# Licznik_sekund.net
KiCad netlist of a schematic drawn in Altium Designer
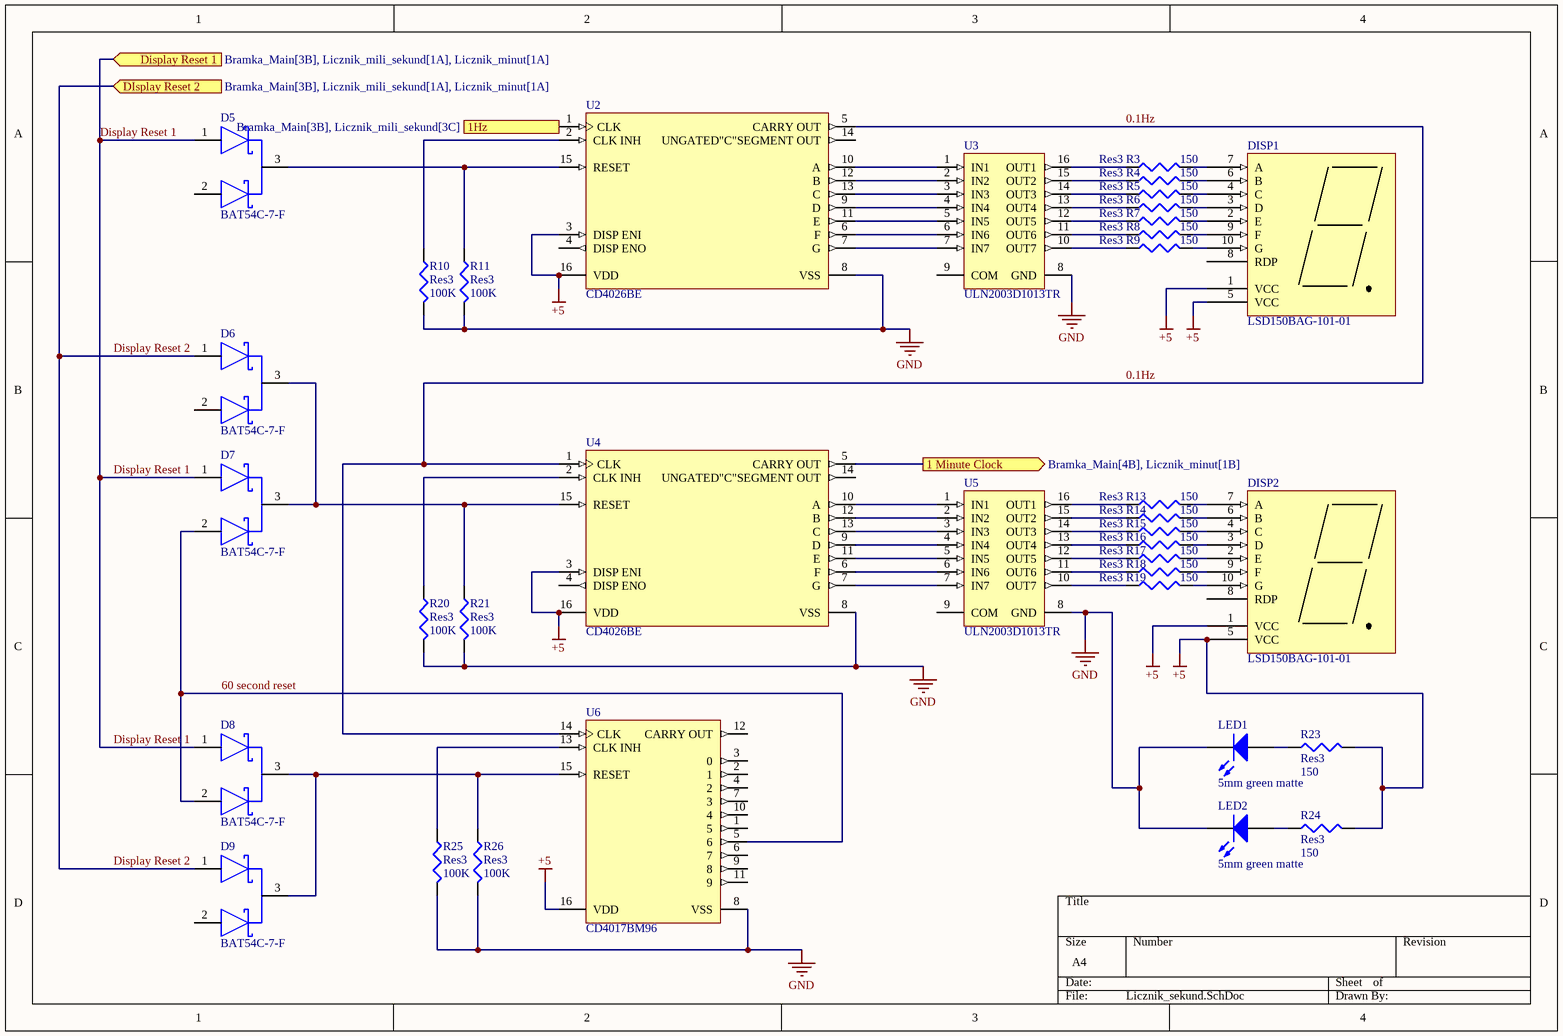
[diagram p0: Licznik_sekund.SchDoc]

(export (version "E")
  (design (tool "Eeschema 10.0.6"))
  (components
    (comp (ref "D5")
      (value "BAT54C-7-F")
      (footprint "FP-SOT23-IPC_B")
      (description "DIODE ARRAY SCHOTTKY 30V SOT23-3")
      (libsource (lib "Altium Content Vault") (part "3eac2aa0c1ac86323ecc23460aa29c6"))
    )
    (comp (ref "D6")
      (value "BAT54C-7-F")
      (footprint "FP-SOT23-IPC_B")
      (description "DIODE ARRAY SCHOTTKY 30V SOT23-3")
      (libsource (lib "Altium Content Vault") (part "3eac2aa0c1ac86323ecc23460aa29c6"))
    )
    (comp (ref "D7")
      (value "BAT54C-7-F")
      (footprint "FP-SOT23-IPC_B")
      (description "DIODE ARRAY SCHOTTKY 30V SOT23-3")
      (libsource (lib "Altium Content Vault") (part "3eac2aa0c1ac86323ecc23460aa29c6"))
    )
    (comp (ref "D8")
      (value "BAT54C-7-F")
      (footprint "FP-SOT23-IPC_B")
      (description "DIODE ARRAY SCHOTTKY 30V SOT23-3")
      (libsource (lib "Altium Content Vault") (part "3eac2aa0c1ac86323ecc23460aa29c6"))
    )
    (comp (ref "D9")
      (value "BAT54C-7-F")
      (footprint "FP-SOT23-IPC_B")
      (description "DIODE ARRAY SCHOTTKY 30V SOT23-3")
      (libsource (lib "Altium Content Vault") (part "3eac2aa0c1ac86323ecc23460aa29c6"))
    )
    (comp (ref "DISP1")
      (value "LSD150BAG-101-01")
      (footprint "7 segment display")
      (description "7 segment display 1.5 inch")
      (libsource (lib "WUST") (part "LSD150BAG-101-01-Symbol-1"))
    )
    (comp (ref "DISP2")
      (value "LSD150BAG-101-01")
      (footprint "7 segment display")
      (description "7 segment display 1.5 inch")
      (libsource (lib "WUST") (part "LSD150BAG-101-01-Symbol-1"))
    )
    (comp (ref "LED1")
      (value "5mm green matte")
      (footprint "Type 5mm")
      (description "THT LED round mono-color color lens, WL-TMRW, Bright Green")
      (fields (field (name "PARTNUMBER") "151051VS04000") (field (name "MANUFACTURER") "Wuerth Elektronik"))
      (libsource (lib "Altium Content Vault") (part "WE-LED_K1A2-2"))
    )
    (comp (ref "LED2")
      (value "5mm green matte")
      (footprint "Type 5mm")
      (description "THT LED round mono-color color lens, WL-TMRW, Bright Green")
      (fields (field (name "PARTNUMBER") "151051VS04000") (field (name "MANUFACTURER") "Wuerth Elektronik"))
      (libsource (lib "Altium Content Vault") (part "WE-LED_K1A2-2"))
    )
    (comp (ref "R3")
      (value "Res3")
      (footprint "6-0805_M")
      (description "Resistor")
      (fields (field (name "ALTIUM_VALUE") "150") (field (name "PUBLISHER") "Altium Limited"))
      (libsource (lib "Miscellaneous Devices") (part "Res3"))
    )
    (comp (ref "R4")
      (value "Res3")
      (footprint "6-0805_M")
      (description "Resistor")
      (fields (field (name "ALTIUM_VALUE") "150") (field (name "PUBLISHER") "Altium Limited"))
      (libsource (lib "Miscellaneous Devices") (part "Res3"))
    )
    (comp (ref "R5")
      (value "Res3")
      (footprint "6-0805_M")
      (description "Resistor")
      (fields (field (name "ALTIUM_VALUE") "150") (field (name "PUBLISHER") "Altium Limited"))
      (libsource (lib "Miscellaneous Devices") (part "Res3"))
    )
    (comp (ref "R6")
      (value "Res3")
      (footprint "6-0805_M")
      (description "Resistor")
      (fields (field (name "ALTIUM_VALUE") "150") (field (name "PUBLISHER") "Altium Limited"))
      (libsource (lib "Miscellaneous Devices") (part "Res3"))
    )
    (comp (ref "R7")
      (value "Res3")
      (footprint "6-0805_M")
      (description "Resistor")
      (fields (field (name "ALTIUM_VALUE") "150") (field (name "PUBLISHER") "Altium Limited"))
      (libsource (lib "Miscellaneous Devices") (part "Res3"))
    )
    (comp (ref "R8")
      (value "Res3")
      (footprint "6-0805_M")
      (description "Resistor")
      (fields (field (name "ALTIUM_VALUE") "150") (field (name "PUBLISHER") "Altium Limited"))
      (libsource (lib "Miscellaneous Devices") (part "Res3"))
    )
    (comp (ref "R9")
      (value "Res3")
      (footprint "6-0805_M")
      (description "Resistor")
      (fields (field (name "ALTIUM_VALUE") "150") (field (name "PUBLISHER") "Altium Limited"))
      (libsource (lib "Miscellaneous Devices") (part "Res3"))
    )
    (comp (ref "R10")
      (value "Res3")
      (footprint "J1-0603")
      (description "Resistor")
      (fields (field (name "ALTIUM_VALUE") "100K") (field (name "PUBLISHER") "Altium Limited"))
      (libsource (lib "Miscellaneous Devices") (part "Res3"))
    )
    (comp (ref "R11")
      (value "Res3")
      (footprint "J1-0603")
      (description "Resistor")
      (fields (field (name "ALTIUM_VALUE") "100K") (field (name "PUBLISHER") "Altium Limited"))
      (libsource (lib "Miscellaneous Devices") (part "Res3"))
    )
    (comp (ref "R13")
      (value "Res3")
      (footprint "6-0805_M")
      (description "Resistor")
      (fields (field (name "ALTIUM_VALUE") "150") (field (name "PUBLISHER") "Altium Limited"))
      (libsource (lib "Miscellaneous Devices") (part "Res3"))
    )
    (comp (ref "R14")
      (value "Res3")
      (footprint "6-0805_M")
      (description "Resistor")
      (fields (field (name "ALTIUM_VALUE") "150") (field (name "PUBLISHER") "Altium Limited"))
      (libsource (lib "Miscellaneous Devices") (part "Res3"))
    )
    (comp (ref "R15")
      (value "Res3")
      (footprint "6-0805_M")
      (description "Resistor")
      (fields (field (name "ALTIUM_VALUE") "150") (field (name "PUBLISHER") "Altium Limited"))
      (libsource (lib "Miscellaneous Devices") (part "Res3"))
    )
    (comp (ref "R16")
      (value "Res3")
      (footprint "6-0805_M")
      (description "Resistor")
      (fields (field (name "ALTIUM_VALUE") "150") (field (name "PUBLISHER") "Altium Limited"))
      (libsource (lib "Miscellaneous Devices") (part "Res3"))
    )
    (comp (ref "R17")
      (value "Res3")
      (footprint "6-0805_M")
      (description "Resistor")
      (fields (field (name "ALTIUM_VALUE") "150") (field (name "PUBLISHER") "Altium Limited"))
      (libsource (lib "Miscellaneous Devices") (part "Res3"))
    )
    (comp (ref "R18")
      (value "Res3")
      (footprint "6-0805_M")
      (description "Resistor")
      (fields (field (name "ALTIUM_VALUE") "150") (field (name "PUBLISHER") "Altium Limited"))
      (libsource (lib "Miscellaneous Devices") (part "Res3"))
    )
    (comp (ref "R19")
      (value "Res3")
      (footprint "6-0805_M")
      (description "Resistor")
      (fields (field (name "ALTIUM_VALUE") "150") (field (name "PUBLISHER") "Altium Limited"))
      (libsource (lib "Miscellaneous Devices") (part "Res3"))
    )
    (comp (ref "R20")
      (value "Res3")
      (footprint "J1-0603")
      (description "Resistor")
      (fields (field (name "ALTIUM_VALUE") "100K") (field (name "PUBLISHER") "Altium Limited"))
      (libsource (lib "Miscellaneous Devices") (part "Res3"))
    )
    (comp (ref "R21")
      (value "Res3")
      (footprint "J1-0603")
      (description "Resistor")
      (fields (field (name "ALTIUM_VALUE") "100K") (field (name "PUBLISHER") "Altium Limited"))
      (libsource (lib "Miscellaneous Devices") (part "Res3"))
    )
    (comp (ref "R23")
      (value "Res3")
      (footprint "6-0805_M")
      (description "Resistor")
      (fields (field (name "ALTIUM_VALUE") "150") (field (name "PUBLISHER") "Altium Limited"))
      (libsource (lib "Miscellaneous Devices") (part "Res3"))
    )
    (comp (ref "R24")
      (value "Res3")
      (footprint "6-0805_M")
      (description "Resistor")
      (fields (field (name "ALTIUM_VALUE") "150") (field (name "PUBLISHER") "Altium Limited"))
      (libsource (lib "Miscellaneous Devices") (part "Res3"))
    )
    (comp (ref "R25")
      (value "Res3")
      (footprint "J1-0603")
      (description "Resistor")
      (fields (field (name "ALTIUM_VALUE") "100K") (field (name "PUBLISHER") "Altium Limited"))
      (libsource (lib "Miscellaneous Devices") (part "Res3"))
    )
    (comp (ref "R26")
      (value "Res3")
      (footprint "J1-0603")
      (description "Resistor")
      (fields (field (name "ALTIUM_VALUE") "100K") (field (name "PUBLISHER") "Altium Limited"))
      (libsource (lib "Miscellaneous Devices") (part "Res3"))
    )
    (comp (ref "U2")
      (value "CD4026BE")
      (footprint "N0016A")
      (fields
        (field (name "MANUFACTURER") "Texas Instruments")
        (field (name "GENERIC PART NUMBER") "CD4026B")
      )
      (libsource (lib "Altium Content Vault") (part "TI-CD4026B-16"))
    )
    (comp (ref "U3")
      (value "ULN2003D1013TR")
      (footprint "STM-SO-16_M")
      (fields (field (name "MANUFACTURER") "STMicroelectronics"))
      (libsource (lib "Altium Content Vault") (part "STM-ULN2003A-PDIP-16"))
    )
    (comp (ref "U4")
      (value "CD4026BE")
      (footprint "N0016A")
      (fields
        (field (name "MANUFACTURER") "Texas Instruments")
        (field (name "GENERIC PART NUMBER") "CD4026B")
      )
      (libsource (lib "Altium Content Vault") (part "TI-CD4026B-16"))
    )
    (comp (ref "U5")
      (value "ULN2003D1013TR")
      (footprint "STM-SO-16_M")
      (fields (field (name "MANUFACTURER") "STMicroelectronics"))
      (libsource (lib "Altium Content Vault") (part "STM-ULN2003A-PDIP-16"))
    )
    (comp (ref "U6")
      (value "CD4017BM96")
      (footprint "D0016A_L")
      (description "CMOS Decade Counter with 10 Decoded Outputs, D0016A, LARGE T&R")
      (fields
        (field (name "GENERIC PART NUMBER") "CD4017B")
        (field (name "MANUFACTURER") "Texas Instruments")
      )
      (libsource (lib "Altium Content Vault") (part "TI-CD4017B-16"))
    )
  )
  (nets
    (net (code "1") (name "+5") (class "Default")
      (node (ref "DISP1") (pin "1") (pinfunction "VCC_1") (pintype "power_in"))
      (node (ref "DISP1") (pin "5") (pinfunction "VCC_5") (pintype "power_in"))
      (node (ref "DISP2") (pin "1") (pinfunction "VCC_1") (pintype "power_in"))
      (node (ref "DISP2") (pin "5") (pinfunction "VCC_5") (pintype "power_in"))
      (node (ref "R23") (pin "2") (pinfunction "2_2") (pintype "passive"))
      (node (ref "R24") (pin "2") (pinfunction "2_2") (pintype "passive"))
      (node (ref "U2") (pin "16") (pinfunction "VDD_16") (pintype "power_in"))
      (node (ref "U2") (pin "3") (pinfunction "DISP_ENI_3") (pintype "input"))
      (node (ref "U4") (pin "16") (pinfunction "VDD_16") (pintype "power_in"))
      (node (ref "U4") (pin "3") (pinfunction "DISP_ENI_3") (pintype "input"))
      (node (ref "U6") (pin "16") (pinfunction "VDD_16") (pintype "power_in"))
    )
    (net (code "2") (name "/0.1Hz") (class "Default")
      (node (ref "U2") (pin "5") (pinfunction "CARRY_OUT_5") (pintype "output"))
      (node (ref "U4") (pin "1") (pinfunction "CLK_1") (pintype "input"))
      (node (ref "U6") (pin "14") (pinfunction "CLK_14") (pintype "input"))
    )
    (net (code "3") (name "/1 Minute Clock") (class "Default")
      (node (ref "U4") (pin "5") (pinfunction "CARRY_OUT_5") (pintype "output"))
    )
    (net (code "4") (name "/1Hz") (class "Default")
      (node (ref "U2") (pin "1") (pinfunction "CLK_1") (pintype "input"))
    )
    (net (code "5") (name "/60 second reset") (class "Default")
      (node (ref "D7") (pin "2") (pinfunction "2_ANODE_2") (pintype "passive"))
      (node (ref "D8") (pin "2") (pinfunction "2_ANODE_2") (pintype "passive"))
      (node (ref "U6") (pin "5") (pinfunction "6_5") (pintype "output"))
    )
    (net (code "6") (name "/Display Reset 1") (class "Default")
      (node (ref "D5") (pin "1") (pinfunction "1_ANODE_1") (pintype "passive"))
      (node (ref "D7") (pin "1") (pinfunction "1_ANODE_1") (pintype "passive"))
      (node (ref "D8") (pin "1") (pinfunction "1_ANODE_1") (pintype "passive"))
    )
    (net (code "7") (name "/Display Reset 2") (class "Default")
      (node (ref "D6") (pin "1") (pinfunction "1_ANODE_1") (pintype "passive"))
      (node (ref "D9") (pin "1") (pinfunction "1_ANODE_1") (pintype "passive"))
    )
    (net (code "8") (name "GND") (class "Default")
      (node (ref "LED1") (pin "1") (pinfunction "K_1") (pintype "passive"))
      (node (ref "LED2") (pin "1") (pinfunction "K_1") (pintype "passive"))
      (node (ref "R10") (pin "2") (pinfunction "2_2") (pintype "passive"))
      (node (ref "R11") (pin "2") (pinfunction "2_2") (pintype "passive"))
      (node (ref "R20") (pin "2") (pinfunction "2_2") (pintype "passive"))
      (node (ref "R21") (pin "2") (pinfunction "2_2") (pintype "passive"))
      (node (ref "R25") (pin "2") (pinfunction "2_2") (pintype "passive"))
      (node (ref "R26") (pin "2") (pinfunction "2_2") (pintype "passive"))
      (node (ref "U2") (pin "8") (pinfunction "VSS_8") (pintype "power_in"))
      (node (ref "U3") (pin "8") (pinfunction "GND_8") (pintype "power_in"))
      (node (ref "U4") (pin "8") (pinfunction "VSS_8") (pintype "power_in"))
      (node (ref "U5") (pin "8") (pinfunction "GND_8") (pintype "power_in"))
      (node (ref "U6") (pin "8") (pinfunction "VSS_8") (pintype "power_in"))
    )
    (net (code "9") (name "Net-(D5-COMMON_CATHODE)") (class "Default")
      (node (ref "D5") (pin "3") (pinfunction "COMMON_CATHODE_3") (pintype "passive"))
      (node (ref "R11") (pin "1") (pinfunction "1_1") (pintype "passive"))
      (node (ref "U2") (pin "15") (pinfunction "RESET_15") (pintype "input"))
    )
    (net (code "10") (name "Net-(D6-COMMON_CATHODE)") (class "Default")
      (node (ref "D6") (pin "3") (pinfunction "COMMON_CATHODE_3") (pintype "passive"))
      (node (ref "D7") (pin "3") (pinfunction "COMMON_CATHODE_3") (pintype "passive"))
      (node (ref "R21") (pin "1") (pinfunction "1_1") (pintype "passive"))
      (node (ref "U4") (pin "15") (pinfunction "RESET_15") (pintype "input"))
    )
    (net (code "11") (name "Net-(D8-COMMON_CATHODE)") (class "Default")
      (node (ref "D8") (pin "3") (pinfunction "COMMON_CATHODE_3") (pintype "passive"))
      (node (ref "D9") (pin "3") (pinfunction "COMMON_CATHODE_3") (pintype "passive"))
      (node (ref "R26") (pin "1") (pinfunction "1_1") (pintype "passive"))
      (node (ref "U6") (pin "15") (pinfunction "RESET_15") (pintype "input"))
    )
    (net (code "12") (name "Net-(DISP1-A)") (class "Default")
      (node (ref "DISP1") (pin "7") (pinfunction "A_7") (pintype "input"))
      (node (ref "R3") (pin "2") (pinfunction "2_2") (pintype "passive"))
    )
    (net (code "13") (name "Net-(DISP1-B)") (class "Default")
      (node (ref "DISP1") (pin "6") (pinfunction "B_6") (pintype "input"))
      (node (ref "R4") (pin "2") (pinfunction "2_2") (pintype "passive"))
    )
    (net (code "14") (name "Net-(DISP1-C)") (class "Default")
      (node (ref "DISP1") (pin "4") (pinfunction "C_4") (pintype "input"))
      (node (ref "R5") (pin "2") (pinfunction "2_2") (pintype "passive"))
    )
    (net (code "15") (name "Net-(DISP1-D)") (class "Default")
      (node (ref "DISP1") (pin "3") (pinfunction "D_3") (pintype "input"))
      (node (ref "R6") (pin "2") (pinfunction "2_2") (pintype "passive"))
    )
    (net (code "16") (name "Net-(DISP1-E)") (class "Default")
      (node (ref "DISP1") (pin "2") (pinfunction "E_2") (pintype "input"))
      (node (ref "R7") (pin "2") (pinfunction "2_2") (pintype "passive"))
    )
    (net (code "17") (name "Net-(DISP1-F)") (class "Default")
      (node (ref "DISP1") (pin "9") (pinfunction "F_9") (pintype "input"))
      (node (ref "R8") (pin "2") (pinfunction "2_2") (pintype "passive"))
    )
    (net (code "18") (name "Net-(DISP1-G)") (class "Default")
      (node (ref "DISP1") (pin "10") (pinfunction "G_10") (pintype "input"))
      (node (ref "R9") (pin "2") (pinfunction "2_2") (pintype "passive"))
    )
    (net (code "19") (name "Net-(DISP2-A)") (class "Default")
      (node (ref "DISP2") (pin "7") (pinfunction "A_7") (pintype "input"))
      (node (ref "R13") (pin "2") (pinfunction "2_2") (pintype "passive"))
    )
    (net (code "20") (name "Net-(DISP2-B)") (class "Default")
      (node (ref "DISP2") (pin "6") (pinfunction "B_6") (pintype "input"))
      (node (ref "R14") (pin "2") (pinfunction "2_2") (pintype "passive"))
    )
    (net (code "21") (name "Net-(DISP2-C)") (class "Default")
      (node (ref "DISP2") (pin "4") (pinfunction "C_4") (pintype "input"))
      (node (ref "R15") (pin "2") (pinfunction "2_2") (pintype "passive"))
    )
    (net (code "22") (name "Net-(DISP2-D)") (class "Default")
      (node (ref "DISP2") (pin "3") (pinfunction "D_3") (pintype "input"))
      (node (ref "R16") (pin "2") (pinfunction "2_2") (pintype "passive"))
    )
    (net (code "23") (name "Net-(DISP2-E)") (class "Default")
      (node (ref "DISP2") (pin "2") (pinfunction "E_2") (pintype "input"))
      (node (ref "R17") (pin "2") (pinfunction "2_2") (pintype "passive"))
    )
    (net (code "24") (name "Net-(DISP2-F)") (class "Default")
      (node (ref "DISP2") (pin "9") (pinfunction "F_9") (pintype "input"))
      (node (ref "R18") (pin "2") (pinfunction "2_2") (pintype "passive"))
    )
    (net (code "25") (name "Net-(DISP2-G)") (class "Default")
      (node (ref "DISP2") (pin "10") (pinfunction "G_10") (pintype "input"))
      (node (ref "R19") (pin "2") (pinfunction "2_2") (pintype "passive"))
    )
    (net (code "26") (name "Net-(LED1-A)") (class "Default")
      (node (ref "LED1") (pin "2") (pinfunction "A_2") (pintype "passive"))
      (node (ref "R23") (pin "1") (pinfunction "1_1") (pintype "passive"))
    )
    (net (code "27") (name "Net-(LED2-A)") (class "Default")
      (node (ref "LED2") (pin "2") (pinfunction "A_2") (pintype "passive"))
      (node (ref "R24") (pin "1") (pinfunction "1_1") (pintype "passive"))
    )
    (net (code "28") (name "Net-(U2-A)") (class "Default")
      (node (ref "U2") (pin "10") (pinfunction "A_10") (pintype "output"))
      (node (ref "U3") (pin "1") (pinfunction "IN1_1") (pintype "input"))
    )
    (net (code "29") (name "Net-(U2-B)") (class "Default")
      (node (ref "U2") (pin "12") (pinfunction "B_12") (pintype "output"))
      (node (ref "U3") (pin "2") (pinfunction "IN2_2") (pintype "input"))
    )
    (net (code "30") (name "Net-(U2-C)") (class "Default")
      (node (ref "U2") (pin "13") (pinfunction "C_13") (pintype "output"))
      (node (ref "U3") (pin "3") (pinfunction "IN3_3") (pintype "input"))
    )
    (net (code "31") (name "Net-(U2-CLK_INH)") (class "Default")
      (node (ref "R10") (pin "1") (pinfunction "1_1") (pintype "passive"))
      (node (ref "U2") (pin "2") (pinfunction "CLK_INH_2") (pintype "input"))
    )
    (net (code "32") (name "Net-(U2-D)") (class "Default")
      (node (ref "U2") (pin "9") (pinfunction "D_9") (pintype "output"))
      (node (ref "U3") (pin "4") (pinfunction "IN4_4") (pintype "input"))
    )
    (net (code "33") (name "Net-(U2-E)") (class "Default")
      (node (ref "U2") (pin "11") (pinfunction "E_11") (pintype "output"))
      (node (ref "U3") (pin "5") (pinfunction "IN5_5") (pintype "input"))
    )
    (net (code "34") (name "Net-(U2-F)") (class "Default")
      (node (ref "U2") (pin "6") (pinfunction "F_6") (pintype "output"))
      (node (ref "U3") (pin "6") (pinfunction "IN6_6") (pintype "input"))
    )
    (net (code "35") (name "Net-(U2-G)") (class "Default")
      (node (ref "U2") (pin "7") (pinfunction "G_7") (pintype "output"))
      (node (ref "U3") (pin "7") (pinfunction "IN7_7") (pintype "input"))
    )
    (net (code "36") (name "Net-(U3-OUT1)") (class "Default")
      (node (ref "R3") (pin "1") (pinfunction "1_1") (pintype "passive"))
      (node (ref "U3") (pin "16") (pinfunction "OUT1_16") (pintype "output"))
    )
    (net (code "37") (name "Net-(U3-OUT2)") (class "Default")
      (node (ref "R4") (pin "1") (pinfunction "1_1") (pintype "passive"))
      (node (ref "U3") (pin "15") (pinfunction "OUT2_15") (pintype "output"))
    )
    (net (code "38") (name "Net-(U3-OUT3)") (class "Default")
      (node (ref "R5") (pin "1") (pinfunction "1_1") (pintype "passive"))
      (node (ref "U3") (pin "14") (pinfunction "OUT3_14") (pintype "output"))
    )
    (net (code "39") (name "Net-(U3-OUT4)") (class "Default")
      (node (ref "R6") (pin "1") (pinfunction "1_1") (pintype "passive"))
      (node (ref "U3") (pin "13") (pinfunction "OUT4_13") (pintype "output"))
    )
    (net (code "40") (name "Net-(U3-OUT5)") (class "Default")
      (node (ref "R7") (pin "1") (pinfunction "1_1") (pintype "passive"))
      (node (ref "U3") (pin "12") (pinfunction "OUT5_12") (pintype "output"))
    )
    (net (code "41") (name "Net-(U3-OUT6)") (class "Default")
      (node (ref "R8") (pin "1") (pinfunction "1_1") (pintype "passive"))
      (node (ref "U3") (pin "11") (pinfunction "OUT6_11") (pintype "output"))
    )
    (net (code "42") (name "Net-(U3-OUT7)") (class "Default")
      (node (ref "R9") (pin "1") (pinfunction "1_1") (pintype "passive"))
      (node (ref "U3") (pin "10") (pinfunction "OUT7_10") (pintype "output"))
    )
    (net (code "43") (name "Net-(U4-A)") (class "Default")
      (node (ref "U4") (pin "10") (pinfunction "A_10") (pintype "output"))
      (node (ref "U5") (pin "1") (pinfunction "IN1_1") (pintype "input"))
    )
    (net (code "44") (name "Net-(U4-B)") (class "Default")
      (node (ref "U4") (pin "12") (pinfunction "B_12") (pintype "output"))
      (node (ref "U5") (pin "2") (pinfunction "IN2_2") (pintype "input"))
    )
    (net (code "45") (name "Net-(U4-C)") (class "Default")
      (node (ref "U4") (pin "13") (pinfunction "C_13") (pintype "output"))
      (node (ref "U5") (pin "3") (pinfunction "IN3_3") (pintype "input"))
    )
    (net (code "46") (name "Net-(U4-CLK_INH)") (class "Default")
      (node (ref "R20") (pin "1") (pinfunction "1_1") (pintype "passive"))
      (node (ref "U4") (pin "2") (pinfunction "CLK_INH_2") (pintype "input"))
    )
    (net (code "47") (name "Net-(U4-D)") (class "Default")
      (node (ref "U4") (pin "9") (pinfunction "D_9") (pintype "output"))
      (node (ref "U5") (pin "4") (pinfunction "IN4_4") (pintype "input"))
    )
    (net (code "48") (name "Net-(U4-E)") (class "Default")
      (node (ref "U4") (pin "11") (pinfunction "E_11") (pintype "output"))
      (node (ref "U5") (pin "5") (pinfunction "IN5_5") (pintype "input"))
    )
    (net (code "49") (name "Net-(U4-F)") (class "Default")
      (node (ref "U4") (pin "6") (pinfunction "F_6") (pintype "output"))
      (node (ref "U5") (pin "6") (pinfunction "IN6_6") (pintype "input"))
    )
    (net (code "50") (name "Net-(U4-G)") (class "Default")
      (node (ref "U4") (pin "7") (pinfunction "G_7") (pintype "output"))
      (node (ref "U5") (pin "7") (pinfunction "IN7_7") (pintype "input"))
    )
    (net (code "51") (name "Net-(U5-OUT1)") (class "Default")
      (node (ref "R13") (pin "1") (pinfunction "1_1") (pintype "passive"))
      (node (ref "U5") (pin "16") (pinfunction "OUT1_16") (pintype "output"))
    )
    (net (code "52") (name "Net-(U5-OUT2)") (class "Default")
      (node (ref "R14") (pin "1") (pinfunction "1_1") (pintype "passive"))
      (node (ref "U5") (pin "15") (pinfunction "OUT2_15") (pintype "output"))
    )
    (net (code "53") (name "Net-(U5-OUT3)") (class "Default")
      (node (ref "R15") (pin "1") (pinfunction "1_1") (pintype "passive"))
      (node (ref "U5") (pin "14") (pinfunction "OUT3_14") (pintype "output"))
    )
    (net (code "54") (name "Net-(U5-OUT4)") (class "Default")
      (node (ref "R16") (pin "1") (pinfunction "1_1") (pintype "passive"))
      (node (ref "U5") (pin "13") (pinfunction "OUT4_13") (pintype "output"))
    )
    (net (code "55") (name "Net-(U5-OUT5)") (class "Default")
      (node (ref "R17") (pin "1") (pinfunction "1_1") (pintype "passive"))
      (node (ref "U5") (pin "12") (pinfunction "OUT5_12") (pintype "output"))
    )
    (net (code "56") (name "Net-(U5-OUT6)") (class "Default")
      (node (ref "R18") (pin "1") (pinfunction "1_1") (pintype "passive"))
      (node (ref "U5") (pin "11") (pinfunction "OUT6_11") (pintype "output"))
    )
    (net (code "57") (name "Net-(U5-OUT7)") (class "Default")
      (node (ref "R19") (pin "1") (pinfunction "1_1") (pintype "passive"))
      (node (ref "U5") (pin "10") (pinfunction "OUT7_10") (pintype "output"))
    )
    (net (code "58") (name "Net-(U6-CLK_INH)") (class "Default")
      (node (ref "R25") (pin "1") (pinfunction "1_1") (pintype "passive"))
      (node (ref "U6") (pin "13") (pinfunction "CLK_INH_13") (pintype "input"))
    )
    (net (code "59") (name "unconnected-(D5-2_ANODE-Pad2)") (class "Default")
      (node (ref "D5") (pin "2") (pinfunction "2_ANODE_2") (pintype "passive"))
    )
    (net (code "60") (name "unconnected-(D6-2_ANODE-Pad2)") (class "Default")
      (node (ref "D6") (pin "2") (pinfunction "2_ANODE_2") (pintype "passive"))
    )
    (net (code "61") (name "unconnected-(D9-2_ANODE-Pad2)") (class "Default")
      (node (ref "D9") (pin "2") (pinfunction "2_ANODE_2") (pintype "passive"))
    )
    (net (code "62") (name "unconnected-(DISP1-RDP-Pad8)") (class "Default")
      (node (ref "DISP1") (pin "8") (pinfunction "RDP_8") (pintype "passive"))
    )
    (net (code "63") (name "unconnected-(DISP2-RDP-Pad8)") (class "Default")
      (node (ref "DISP2") (pin "8") (pinfunction "RDP_8") (pintype "passive"))
    )
    (net (code "64") (name "unconnected-(U2-DISP_ENO-Pad4)") (class "Default")
      (node (ref "U2") (pin "4") (pinfunction "DISP_ENO_4") (pintype "output"))
    )
    (net (code "65") (name "unconnected-(U2-UNGATED\"C\"SEGMENT_OUT-Pad14)") (class "Default")
      (node (ref "U2") (pin "14") (pinfunction "UNGATED\"C\"SEGMENT_OUT_14") (pintype "output"))
    )
    (net (code "66") (name "unconnected-(U3-COM-Pad9)") (class "Default")
      (node (ref "U3") (pin "9") (pinfunction "COM_9") (pintype "passive"))
    )
    (net (code "67") (name "unconnected-(U4-DISP_ENO-Pad4)") (class "Default")
      (node (ref "U4") (pin "4") (pinfunction "DISP_ENO_4") (pintype "output"))
    )
    (net (code "68") (name "unconnected-(U4-UNGATED\"C\"SEGMENT_OUT-Pad14)") (class "Default")
      (node (ref "U4") (pin "14") (pinfunction "UNGATED\"C\"SEGMENT_OUT_14") (pintype "output"))
    )
    (net (code "69") (name "unconnected-(U5-COM-Pad9)") (class "Default")
      (node (ref "U5") (pin "9") (pinfunction "COM_9") (pintype "passive"))
    )
    (net (code "70") (name "unconnected-(U6-0-Pad3)") (class "Default")
      (node (ref "U6") (pin "3") (pinfunction "0_3") (pintype "output"))
    )
    (net (code "71") (name "unconnected-(U6-1-Pad2)") (class "Default")
      (node (ref "U6") (pin "2") (pinfunction "1_2") (pintype "output"))
    )
    (net (code "72") (name "unconnected-(U6-2-Pad4)") (class "Default")
      (node (ref "U6") (pin "4") (pinfunction "2_4") (pintype "output"))
    )
    (net (code "73") (name "unconnected-(U6-3-Pad7)") (class "Default")
      (node (ref "U6") (pin "7") (pinfunction "3_7") (pintype "output"))
    )
    (net (code "74") (name "unconnected-(U6-4-Pad10)") (class "Default")
      (node (ref "U6") (pin "10") (pinfunction "4_10") (pintype "output"))
    )
    (net (code "75") (name "unconnected-(U6-5-Pad1)") (class "Default")
      (node (ref "U6") (pin "1") (pinfunction "5_1") (pintype "output"))
    )
    (net (code "76") (name "unconnected-(U6-7-Pad6)") (class "Default")
      (node (ref "U6") (pin "6") (pinfunction "7_6") (pintype "output"))
    )
    (net (code "77") (name "unconnected-(U6-8-Pad9)") (class "Default")
      (node (ref "U6") (pin "9") (pinfunction "8_9") (pintype "output"))
    )
    (net (code "78") (name "unconnected-(U6-9-Pad11)") (class "Default")
      (node (ref "U6") (pin "11") (pinfunction "9_11") (pintype "output"))
    )
    (net (code "79") (name "unconnected-(U6-CARRY_OUT-Pad12)") (class "Default")
      (node (ref "U6") (pin "12") (pinfunction "CARRY_OUT_12") (pintype "output"))
    )
  )
)
